# TOP.net
KiCad netlist of a schematic drawn in Altium Designer
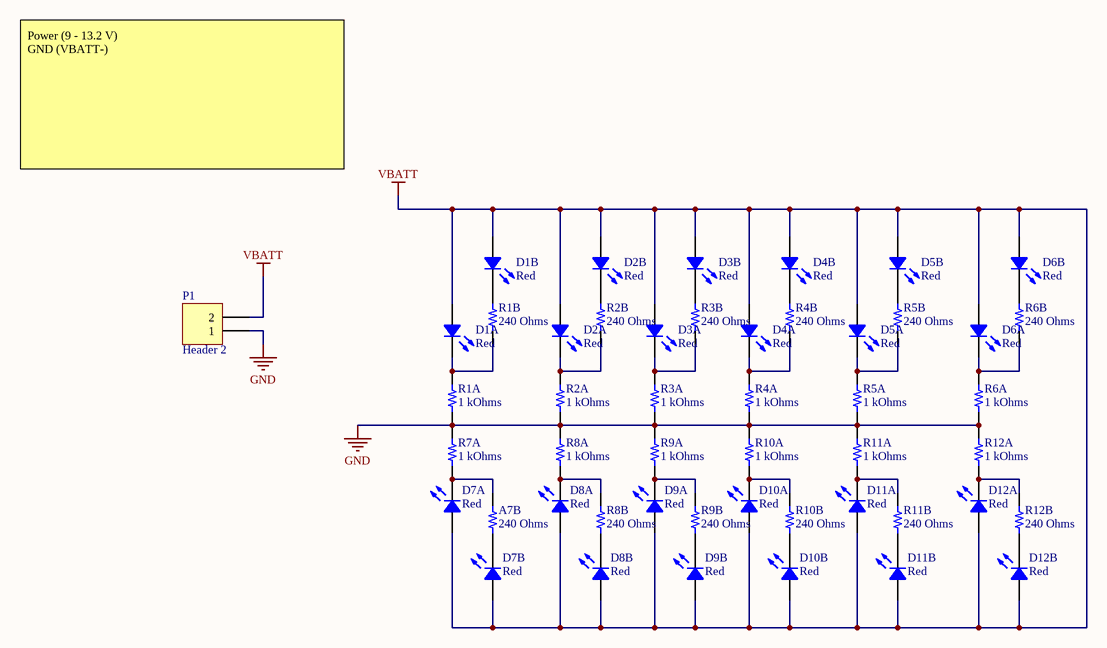
[diagram p0: TOP.SchDoc]

(export (version "E")
  (design (tool "Eeschema 10.0.6"))
  (components
    (comp (ref "A7B")
      (value "240 Ohms")
      (footprint "RES 0402_1005")
      (description "RES 240 OHM 1% 1/16W 0402")
      (fields (field (name "PART NUMBER") "RC0402FR-13240RL") (field (name "MANUFACTURER") "Yageo"))
      (libsource (lib "Celestial") (part "Resistor"))
    )
    (comp (ref "D1A")
      (value "Red")
      (footprint "LED 1206_3216 RED")
      (description "LED SMD")
      (fields (field (name "PART NUMBER") "APTR3216SECK/J3-PRV") (field (name "MANUFACTURER") "Kingbright"))
      (libsource (lib "Celestial") (part "LED"))
    )
    (comp (ref "D1B")
      (value "Red")
      (footprint "LED 1206_3216 RED")
      (description "LED SMD")
      (fields (field (name "PART NUMBER") "APTR3216SECK/J3-PRV") (field (name "MANUFACTURER") "Kingbright"))
      (libsource (lib "Celestial") (part "LED"))
    )
    (comp (ref "D2A")
      (value "Red")
      (footprint "LED 1206_3216 RED")
      (description "LED SMD")
      (fields (field (name "PART NUMBER") "APTR3216SECK/J3-PRV") (field (name "MANUFACTURER") "Kingbright"))
      (libsource (lib "Celestial") (part "LED"))
    )
    (comp (ref "D2B")
      (value "Red")
      (footprint "LED 1206_3216 RED")
      (description "LED SMD")
      (fields (field (name "PART NUMBER") "APTR3216SECK/J3-PRV") (field (name "MANUFACTURER") "Kingbright"))
      (libsource (lib "Celestial") (part "LED"))
    )
    (comp (ref "D3A")
      (value "Red")
      (footprint "LED 1206_3216 RED")
      (description "LED SMD")
      (fields (field (name "PART NUMBER") "APTR3216SECK/J3-PRV") (field (name "MANUFACTURER") "Kingbright"))
      (libsource (lib "Celestial") (part "LED"))
    )
    (comp (ref "D3B")
      (value "Red")
      (footprint "LED 1206_3216 RED")
      (description "LED SMD")
      (fields (field (name "PART NUMBER") "APTR3216SECK/J3-PRV") (field (name "MANUFACTURER") "Kingbright"))
      (libsource (lib "Celestial") (part "LED"))
    )
    (comp (ref "D4A")
      (value "Red")
      (footprint "LED 1206_3216 RED")
      (description "LED SMD")
      (fields (field (name "PART NUMBER") "APTR3216SECK/J3-PRV") (field (name "MANUFACTURER") "Kingbright"))
      (libsource (lib "Celestial") (part "LED"))
    )
    (comp (ref "D4B")
      (value "Red")
      (footprint "LED 1206_3216 RED")
      (description "LED SMD")
      (fields (field (name "PART NUMBER") "APTR3216SECK/J3-PRV") (field (name "MANUFACTURER") "Kingbright"))
      (libsource (lib "Celestial") (part "LED"))
    )
    (comp (ref "D5A")
      (value "Red")
      (footprint "LED 1206_3216 RED")
      (description "LED SMD")
      (fields (field (name "PART NUMBER") "APTR3216SECK/J3-PRV") (field (name "MANUFACTURER") "Kingbright"))
      (libsource (lib "Celestial") (part "LED"))
    )
    (comp (ref "D5B")
      (value "Red")
      (footprint "LED 1206_3216 RED")
      (description "LED SMD")
      (fields (field (name "PART NUMBER") "APTR3216SECK/J3-PRV") (field (name "MANUFACTURER") "Kingbright"))
      (libsource (lib "Celestial") (part "LED"))
    )
    (comp (ref "D6A")
      (value "Red")
      (footprint "LED 1206_3216 RED")
      (description "LED SMD")
      (fields (field (name "PART NUMBER") "APTR3216SECK/J3-PRV") (field (name "MANUFACTURER") "Kingbright"))
      (libsource (lib "Celestial") (part "LED"))
    )
    (comp (ref "D6B")
      (value "Red")
      (footprint "LED 1206_3216 RED")
      (description "LED SMD")
      (fields (field (name "PART NUMBER") "APTR3216SECK/J3-PRV") (field (name "MANUFACTURER") "Kingbright"))
      (libsource (lib "Celestial") (part "LED"))
    )
    (comp (ref "D7A")
      (value "Red")
      (footprint "LED 1206_3216 RED")
      (description "LED SMD")
      (fields (field (name "PART NUMBER") "APTR3216SECK/J3-PRV") (field (name "MANUFACTURER") "Kingbright"))
      (libsource (lib "Celestial") (part "LED"))
    )
    (comp (ref "D7B")
      (value "Red")
      (footprint "LED 1206_3216 RED")
      (description "LED SMD")
      (fields (field (name "PART NUMBER") "APTR3216SECK/J3-PRV") (field (name "MANUFACTURER") "Kingbright"))
      (libsource (lib "Celestial") (part "LED"))
    )
    (comp (ref "D8A")
      (value "Red")
      (footprint "LED 1206_3216 RED")
      (description "LED SMD")
      (fields (field (name "PART NUMBER") "APTR3216SECK/J3-PRV") (field (name "MANUFACTURER") "Kingbright"))
      (libsource (lib "Celestial") (part "LED"))
    )
    (comp (ref "D8B")
      (value "Red")
      (footprint "LED 1206_3216 RED")
      (description "LED SMD")
      (fields (field (name "PART NUMBER") "APTR3216SECK/J3-PRV") (field (name "MANUFACTURER") "Kingbright"))
      (libsource (lib "Celestial") (part "LED"))
    )
    (comp (ref "D9A")
      (value "Red")
      (footprint "LED 1206_3216 RED")
      (description "LED SMD")
      (fields (field (name "PART NUMBER") "APTR3216SECK/J3-PRV") (field (name "MANUFACTURER") "Kingbright"))
      (libsource (lib "Celestial") (part "LED"))
    )
    (comp (ref "D9B")
      (value "Red")
      (footprint "LED 1206_3216 RED")
      (description "LED SMD")
      (fields (field (name "PART NUMBER") "APTR3216SECK/J3-PRV") (field (name "MANUFACTURER") "Kingbright"))
      (libsource (lib "Celestial") (part "LED"))
    )
    (comp (ref "D10A")
      (value "Red")
      (footprint "LED 1206_3216 RED")
      (description "LED SMD")
      (fields (field (name "PART NUMBER") "APTR3216SECK/J3-PRV") (field (name "MANUFACTURER") "Kingbright"))
      (libsource (lib "Celestial") (part "LED"))
    )
    (comp (ref "D10B")
      (value "Red")
      (footprint "LED 1206_3216 RED")
      (description "LED SMD")
      (fields (field (name "PART NUMBER") "APTR3216SECK/J3-PRV") (field (name "MANUFACTURER") "Kingbright"))
      (libsource (lib "Celestial") (part "LED"))
    )
    (comp (ref "D11A")
      (value "Red")
      (footprint "LED 1206_3216 RED")
      (description "LED SMD")
      (fields (field (name "PART NUMBER") "APTR3216SECK/J3-PRV") (field (name "MANUFACTURER") "Kingbright"))
      (libsource (lib "Celestial") (part "LED"))
    )
    (comp (ref "D11B")
      (value "Red")
      (footprint "LED 1206_3216 RED")
      (description "LED SMD")
      (fields (field (name "PART NUMBER") "APTR3216SECK/J3-PRV") (field (name "MANUFACTURER") "Kingbright"))
      (libsource (lib "Celestial") (part "LED"))
    )
    (comp (ref "D12A")
      (value "Red")
      (footprint "LED 1206_3216 RED")
      (description "LED SMD")
      (fields (field (name "PART NUMBER") "APTR3216SECK/J3-PRV") (field (name "MANUFACTURER") "Kingbright"))
      (libsource (lib "Celestial") (part "LED"))
    )
    (comp (ref "D12B")
      (value "Red")
      (footprint "LED 1206_3216 RED")
      (description "LED SMD")
      (fields (field (name "PART NUMBER") "APTR3216SECK/J3-PRV") (field (name "MANUFACTURER") "Kingbright"))
      (libsource (lib "Celestial") (part "LED"))
    )
    (comp (ref "P1")
      (value "Header 2")
      (footprint "HDR1X2")
      (description "Header, 2-Pin")
      (fields (field (name "PUBLISHER") "Altium Limited"))
      (libsource (lib "Miscellaneous Connectors") (part "Header 2"))
    )
    (comp (ref "R1A")
      (value "1 kOhms")
      (footprint "RES 0402_1005")
      (description "RES SMD 1K OHM 0.1% 1/16W 0402")
      (fields (field (name "PART NUMBER") "AT0402BRD071KL") (field (name "MANUFACTURER") "Yageo"))
      (libsource (lib "Celestial") (part "Resistor"))
    )
    (comp (ref "R1B")
      (value "240 Ohms")
      (footprint "RES 0402_1005")
      (description "RES 240 OHM 1% 1/16W 0402")
      (fields (field (name "PART NUMBER") "RC0402FR-13240RL") (field (name "MANUFACTURER") "Yageo"))
      (libsource (lib "Celestial") (part "Resistor"))
    )
    (comp (ref "R2A")
      (value "1 kOhms")
      (footprint "RES 0402_1005")
      (description "RES SMD 1K OHM 0.1% 1/16W 0402")
      (fields (field (name "PART NUMBER") "AT0402BRD071KL") (field (name "MANUFACTURER") "Yageo"))
      (libsource (lib "Celestial") (part "Resistor"))
    )
    (comp (ref "R2B")
      (value "240 Ohms")
      (footprint "RES 0402_1005")
      (description "RES 240 OHM 1% 1/16W 0402")
      (fields (field (name "PART NUMBER") "RC0402FR-13240RL") (field (name "MANUFACTURER") "Yageo"))
      (libsource (lib "Celestial") (part "Resistor"))
    )
    (comp (ref "R3A")
      (value "1 kOhms")
      (footprint "RES 0402_1005")
      (description "RES SMD 1K OHM 0.1% 1/16W 0402")
      (fields (field (name "PART NUMBER") "AT0402BRD071KL") (field (name "MANUFACTURER") "Yageo"))
      (libsource (lib "Celestial") (part "Resistor"))
    )
    (comp (ref "R3B")
      (value "240 Ohms")
      (footprint "RES 0402_1005")
      (description "RES 240 OHM 1% 1/16W 0402")
      (fields (field (name "PART NUMBER") "RC0402FR-13240RL") (field (name "MANUFACTURER") "Yageo"))
      (libsource (lib "Celestial") (part "Resistor"))
    )
    (comp (ref "R4A")
      (value "1 kOhms")
      (footprint "RES 0402_1005")
      (description "RES SMD 1K OHM 0.1% 1/16W 0402")
      (fields (field (name "PART NUMBER") "AT0402BRD071KL") (field (name "MANUFACTURER") "Yageo"))
      (libsource (lib "Celestial") (part "Resistor"))
    )
    (comp (ref "R4B")
      (value "240 Ohms")
      (footprint "RES 0402_1005")
      (description "RES 240 OHM 1% 1/16W 0402")
      (fields (field (name "PART NUMBER") "RC0402FR-13240RL") (field (name "MANUFACTURER") "Yageo"))
      (libsource (lib "Celestial") (part "Resistor"))
    )
    (comp (ref "R5A")
      (value "1 kOhms")
      (footprint "RES 0402_1005")
      (description "RES SMD 1K OHM 0.1% 1/16W 0402")
      (fields (field (name "PART NUMBER") "AT0402BRD071KL") (field (name "MANUFACTURER") "Yageo"))
      (libsource (lib "Celestial") (part "Resistor"))
    )
    (comp (ref "R5B")
      (value "240 Ohms")
      (footprint "RES 0402_1005")
      (description "RES 240 OHM 1% 1/16W 0402")
      (fields (field (name "PART NUMBER") "RC0402FR-13240RL") (field (name "MANUFACTURER") "Yageo"))
      (libsource (lib "Celestial") (part "Resistor"))
    )
    (comp (ref "R6A")
      (value "1 kOhms")
      (footprint "RES 0402_1005")
      (description "RES SMD 1K OHM 0.1% 1/16W 0402")
      (fields (field (name "PART NUMBER") "AT0402BRD071KL") (field (name "MANUFACTURER") "Yageo"))
      (libsource (lib "Celestial") (part "Resistor"))
    )
    (comp (ref "R6B")
      (value "240 Ohms")
      (footprint "RES 0402_1005")
      (description "RES 240 OHM 1% 1/16W 0402")
      (fields (field (name "PART NUMBER") "RC0402FR-13240RL") (field (name "MANUFACTURER") "Yageo"))
      (libsource (lib "Celestial") (part "Resistor"))
    )
    (comp (ref "R7A")
      (value "1 kOhms")
      (footprint "RES 0402_1005")
      (description "RES SMD 1K OHM 0.1% 1/16W 0402")
      (fields (field (name "PART NUMBER") "AT0402BRD071KL") (field (name "MANUFACTURER") "Yageo"))
      (libsource (lib "Celestial") (part "Resistor"))
    )
    (comp (ref "R8A")
      (value "1 kOhms")
      (footprint "RES 0402_1005")
      (description "RES SMD 1K OHM 0.1% 1/16W 0402")
      (fields (field (name "PART NUMBER") "AT0402BRD071KL") (field (name "MANUFACTURER") "Yageo"))
      (libsource (lib "Celestial") (part "Resistor"))
    )
    (comp (ref "R8B")
      (value "240 Ohms")
      (footprint "RES 0402_1005")
      (description "RES 240 OHM 1% 1/16W 0402")
      (fields (field (name "PART NUMBER") "RC0402FR-13240RL") (field (name "MANUFACTURER") "Yageo"))
      (libsource (lib "Celestial") (part "Resistor"))
    )
    (comp (ref "R9A")
      (value "1 kOhms")
      (footprint "RES 0402_1005")
      (description "RES SMD 1K OHM 0.1% 1/16W 0402")
      (fields (field (name "PART NUMBER") "AT0402BRD071KL") (field (name "MANUFACTURER") "Yageo"))
      (libsource (lib "Celestial") (part "Resistor"))
    )
    (comp (ref "R9B")
      (value "240 Ohms")
      (footprint "RES 0402_1005")
      (description "RES 240 OHM 1% 1/16W 0402")
      (fields (field (name "PART NUMBER") "RC0402FR-13240RL") (field (name "MANUFACTURER") "Yageo"))
      (libsource (lib "Celestial") (part "Resistor"))
    )
    (comp (ref "R10A")
      (value "1 kOhms")
      (footprint "RES 0402_1005")
      (description "RES SMD 1K OHM 0.1% 1/16W 0402")
      (fields (field (name "PART NUMBER") "AT0402BRD071KL") (field (name "MANUFACTURER") "Yageo"))
      (libsource (lib "Celestial") (part "Resistor"))
    )
    (comp (ref "R10B")
      (value "240 Ohms")
      (footprint "RES 0402_1005")
      (description "RES 240 OHM 1% 1/16W 0402")
      (fields (field (name "PART NUMBER") "RC0402FR-13240RL") (field (name "MANUFACTURER") "Yageo"))
      (libsource (lib "Celestial") (part "Resistor"))
    )
    (comp (ref "R11A")
      (value "1 kOhms")
      (footprint "RES 0402_1005")
      (description "RES SMD 1K OHM 0.1% 1/16W 0402")
      (fields (field (name "PART NUMBER") "AT0402BRD071KL") (field (name "MANUFACTURER") "Yageo"))
      (libsource (lib "Celestial") (part "Resistor"))
    )
    (comp (ref "R11B")
      (value "240 Ohms")
      (footprint "RES 0402_1005")
      (description "RES 240 OHM 1% 1/16W 0402")
      (fields (field (name "PART NUMBER") "RC0402FR-13240RL") (field (name "MANUFACTURER") "Yageo"))
      (libsource (lib "Celestial") (part "Resistor"))
    )
    (comp (ref "R12A")
      (value "1 kOhms")
      (footprint "RES 0402_1005")
      (description "RES SMD 1K OHM 0.1% 1/16W 0402")
      (fields (field (name "PART NUMBER") "AT0402BRD071KL") (field (name "MANUFACTURER") "Yageo"))
      (libsource (lib "Celestial") (part "Resistor"))
    )
    (comp (ref "R12B")
      (value "240 Ohms")
      (footprint "RES 0402_1005")
      (description "RES 240 OHM 1% 1/16W 0402")
      (fields (field (name "PART NUMBER") "RC0402FR-13240RL") (field (name "MANUFACTURER") "Yageo"))
      (libsource (lib "Celestial") (part "Resistor"))
    )
  )
  (nets
    (net (code "1") (name "GND") (class "Default")
      (node (ref "P1") (pin "1") (pinfunction "1_1") (pintype "passive"))
      (node (ref "R10A") (pin "2") (pinfunction "2_2") (pintype "passive"))
      (node (ref "R11A") (pin "2") (pinfunction "2_2") (pintype "passive"))
      (node (ref "R12A") (pin "2") (pinfunction "2_2") (pintype "passive"))
      (node (ref "R1A") (pin "1") (pinfunction "1_1") (pintype "passive"))
      (node (ref "R2A") (pin "1") (pinfunction "1_1") (pintype "passive"))
      (node (ref "R3A") (pin "1") (pinfunction "1_1") (pintype "passive"))
      (node (ref "R4A") (pin "1") (pinfunction "1_1") (pintype "passive"))
      (node (ref "R5A") (pin "1") (pinfunction "1_1") (pintype "passive"))
      (node (ref "R6A") (pin "1") (pinfunction "1_1") (pintype "passive"))
      (node (ref "R7A") (pin "2") (pinfunction "2_2") (pintype "passive"))
      (node (ref "R8A") (pin "2") (pinfunction "2_2") (pintype "passive"))
      (node (ref "R9A") (pin "2") (pinfunction "2_2") (pintype "passive"))
    )
    (net (code "2") (name "Net-(A7B-Pad1)") (class "Default")
      (node (ref "A7B") (pin "1") (pinfunction "1_1") (pintype "passive"))
      (node (ref "D7B") (pin "2") (pinfunction "2_2") (pintype "passive"))
    )
    (net (code "3") (name "Net-(A7B-Pad2)") (class "Default")
      (node (ref "A7B") (pin "2") (pinfunction "2_2") (pintype "passive"))
      (node (ref "D7A") (pin "2") (pinfunction "2_2") (pintype "passive"))
      (node (ref "R7A") (pin "1") (pinfunction "1_1") (pintype "passive"))
    )
    (net (code "4") (name "Net-(D1A-Pad2)") (class "Default")
      (node (ref "D1A") (pin "2") (pinfunction "2_2") (pintype "passive"))
      (node (ref "R1A") (pin "2") (pinfunction "2_2") (pintype "passive"))
      (node (ref "R1B") (pin "1") (pinfunction "1_1") (pintype "passive"))
    )
    (net (code "5") (name "Net-(D1B-Pad2)") (class "Default")
      (node (ref "D1B") (pin "2") (pinfunction "2_2") (pintype "passive"))
      (node (ref "R1B") (pin "2") (pinfunction "2_2") (pintype "passive"))
    )
    (net (code "6") (name "Net-(D2A-Pad2)") (class "Default")
      (node (ref "D2A") (pin "2") (pinfunction "2_2") (pintype "passive"))
      (node (ref "R2A") (pin "2") (pinfunction "2_2") (pintype "passive"))
      (node (ref "R2B") (pin "1") (pinfunction "1_1") (pintype "passive"))
    )
    (net (code "7") (name "Net-(D2B-Pad2)") (class "Default")
      (node (ref "D2B") (pin "2") (pinfunction "2_2") (pintype "passive"))
      (node (ref "R2B") (pin "2") (pinfunction "2_2") (pintype "passive"))
    )
    (net (code "8") (name "Net-(D3A-Pad2)") (class "Default")
      (node (ref "D3A") (pin "2") (pinfunction "2_2") (pintype "passive"))
      (node (ref "R3A") (pin "2") (pinfunction "2_2") (pintype "passive"))
      (node (ref "R3B") (pin "1") (pinfunction "1_1") (pintype "passive"))
    )
    (net (code "9") (name "Net-(D3B-Pad2)") (class "Default")
      (node (ref "D3B") (pin "2") (pinfunction "2_2") (pintype "passive"))
      (node (ref "R3B") (pin "2") (pinfunction "2_2") (pintype "passive"))
    )
    (net (code "10") (name "Net-(D4A-Pad2)") (class "Default")
      (node (ref "D4A") (pin "2") (pinfunction "2_2") (pintype "passive"))
      (node (ref "R4A") (pin "2") (pinfunction "2_2") (pintype "passive"))
      (node (ref "R4B") (pin "1") (pinfunction "1_1") (pintype "passive"))
    )
    (net (code "11") (name "Net-(D4B-Pad2)") (class "Default")
      (node (ref "D4B") (pin "2") (pinfunction "2_2") (pintype "passive"))
      (node (ref "R4B") (pin "2") (pinfunction "2_2") (pintype "passive"))
    )
    (net (code "12") (name "Net-(D5A-Pad2)") (class "Default")
      (node (ref "D5A") (pin "2") (pinfunction "2_2") (pintype "passive"))
      (node (ref "R5A") (pin "2") (pinfunction "2_2") (pintype "passive"))
      (node (ref "R5B") (pin "1") (pinfunction "1_1") (pintype "passive"))
    )
    (net (code "13") (name "Net-(D5B-Pad2)") (class "Default")
      (node (ref "D5B") (pin "2") (pinfunction "2_2") (pintype "passive"))
      (node (ref "R5B") (pin "2") (pinfunction "2_2") (pintype "passive"))
    )
    (net (code "14") (name "Net-(D6A-Pad2)") (class "Default")
      (node (ref "D6A") (pin "2") (pinfunction "2_2") (pintype "passive"))
      (node (ref "R6A") (pin "2") (pinfunction "2_2") (pintype "passive"))
      (node (ref "R6B") (pin "1") (pinfunction "1_1") (pintype "passive"))
    )
    (net (code "15") (name "Net-(D6B-Pad2)") (class "Default")
      (node (ref "D6B") (pin "2") (pinfunction "2_2") (pintype "passive"))
      (node (ref "R6B") (pin "2") (pinfunction "2_2") (pintype "passive"))
    )
    (net (code "16") (name "Net-(D8A-Pad2)") (class "Default")
      (node (ref "D8A") (pin "2") (pinfunction "2_2") (pintype "passive"))
      (node (ref "R8A") (pin "1") (pinfunction "1_1") (pintype "passive"))
      (node (ref "R8B") (pin "2") (pinfunction "2_2") (pintype "passive"))
    )
    (net (code "17") (name "Net-(D8B-Pad2)") (class "Default")
      (node (ref "D8B") (pin "2") (pinfunction "2_2") (pintype "passive"))
      (node (ref "R8B") (pin "1") (pinfunction "1_1") (pintype "passive"))
    )
    (net (code "18") (name "Net-(D9A-Pad2)") (class "Default")
      (node (ref "D9A") (pin "2") (pinfunction "2_2") (pintype "passive"))
      (node (ref "R9A") (pin "1") (pinfunction "1_1") (pintype "passive"))
      (node (ref "R9B") (pin "2") (pinfunction "2_2") (pintype "passive"))
    )
    (net (code "19") (name "Net-(D9B-Pad2)") (class "Default")
      (node (ref "D9B") (pin "2") (pinfunction "2_2") (pintype "passive"))
      (node (ref "R9B") (pin "1") (pinfunction "1_1") (pintype "passive"))
    )
    (net (code "20") (name "Net-(D10A-Pad2)") (class "Default")
      (node (ref "D10A") (pin "2") (pinfunction "2_2") (pintype "passive"))
      (node (ref "R10A") (pin "1") (pinfunction "1_1") (pintype "passive"))
      (node (ref "R10B") (pin "2") (pinfunction "2_2") (pintype "passive"))
    )
    (net (code "21") (name "Net-(D10B-Pad2)") (class "Default")
      (node (ref "D10B") (pin "2") (pinfunction "2_2") (pintype "passive"))
      (node (ref "R10B") (pin "1") (pinfunction "1_1") (pintype "passive"))
    )
    (net (code "22") (name "Net-(D11A-Pad2)") (class "Default")
      (node (ref "D11A") (pin "2") (pinfunction "2_2") (pintype "passive"))
      (node (ref "R11A") (pin "1") (pinfunction "1_1") (pintype "passive"))
      (node (ref "R11B") (pin "2") (pinfunction "2_2") (pintype "passive"))
    )
    (net (code "23") (name "Net-(D11B-Pad2)") (class "Default")
      (node (ref "D11B") (pin "2") (pinfunction "2_2") (pintype "passive"))
      (node (ref "R11B") (pin "1") (pinfunction "1_1") (pintype "passive"))
    )
    (net (code "24") (name "Net-(D12A-Pad2)") (class "Default")
      (node (ref "D12A") (pin "2") (pinfunction "2_2") (pintype "passive"))
      (node (ref "R12A") (pin "1") (pinfunction "1_1") (pintype "passive"))
      (node (ref "R12B") (pin "2") (pinfunction "2_2") (pintype "passive"))
    )
    (net (code "25") (name "Net-(D12B-Pad2)") (class "Default")
      (node (ref "D12B") (pin "2") (pinfunction "2_2") (pintype "passive"))
      (node (ref "R12B") (pin "1") (pinfunction "1_1") (pintype "passive"))
    )
    (net (code "26") (name "VBATT") (class "Default")
      (node (ref "D10A") (pin "1") (pinfunction "1_1") (pintype "passive"))
      (node (ref "D10B") (pin "1") (pinfunction "1_1") (pintype "passive"))
      (node (ref "D11A") (pin "1") (pinfunction "1_1") (pintype "passive"))
      (node (ref "D11B") (pin "1") (pinfunction "1_1") (pintype "passive"))
      (node (ref "D12A") (pin "1") (pinfunction "1_1") (pintype "passive"))
      (node (ref "D12B") (pin "1") (pinfunction "1_1") (pintype "passive"))
      (node (ref "D1A") (pin "1") (pinfunction "1_1") (pintype "passive"))
      (node (ref "D1B") (pin "1") (pinfunction "1_1") (pintype "passive"))
      (node (ref "D2A") (pin "1") (pinfunction "1_1") (pintype "passive"))
      (node (ref "D2B") (pin "1") (pinfunction "1_1") (pintype "passive"))
      (node (ref "D3A") (pin "1") (pinfunction "1_1") (pintype "passive"))
      (node (ref "D3B") (pin "1") (pinfunction "1_1") (pintype "passive"))
      (node (ref "D4A") (pin "1") (pinfunction "1_1") (pintype "passive"))
      (node (ref "D4B") (pin "1") (pinfunction "1_1") (pintype "passive"))
      (node (ref "D5A") (pin "1") (pinfunction "1_1") (pintype "passive"))
      (node (ref "D5B") (pin "1") (pinfunction "1_1") (pintype "passive"))
      (node (ref "D6A") (pin "1") (pinfunction "1_1") (pintype "passive"))
      (node (ref "D6B") (pin "1") (pinfunction "1_1") (pintype "passive"))
      (node (ref "D7A") (pin "1") (pinfunction "1_1") (pintype "passive"))
      (node (ref "D7B") (pin "1") (pinfunction "1_1") (pintype "passive"))
      (node (ref "D8A") (pin "1") (pinfunction "1_1") (pintype "passive"))
      (node (ref "D8B") (pin "1") (pinfunction "1_1") (pintype "passive"))
      (node (ref "D9A") (pin "1") (pinfunction "1_1") (pintype "passive"))
      (node (ref "D9B") (pin "1") (pinfunction "1_1") (pintype "passive"))
      (node (ref "P1") (pin "2") (pinfunction "2_2") (pintype "passive"))
    )
  )
)
